# ACS_PCB.net
KiCad netlist of a schematic drawn in EAGLE
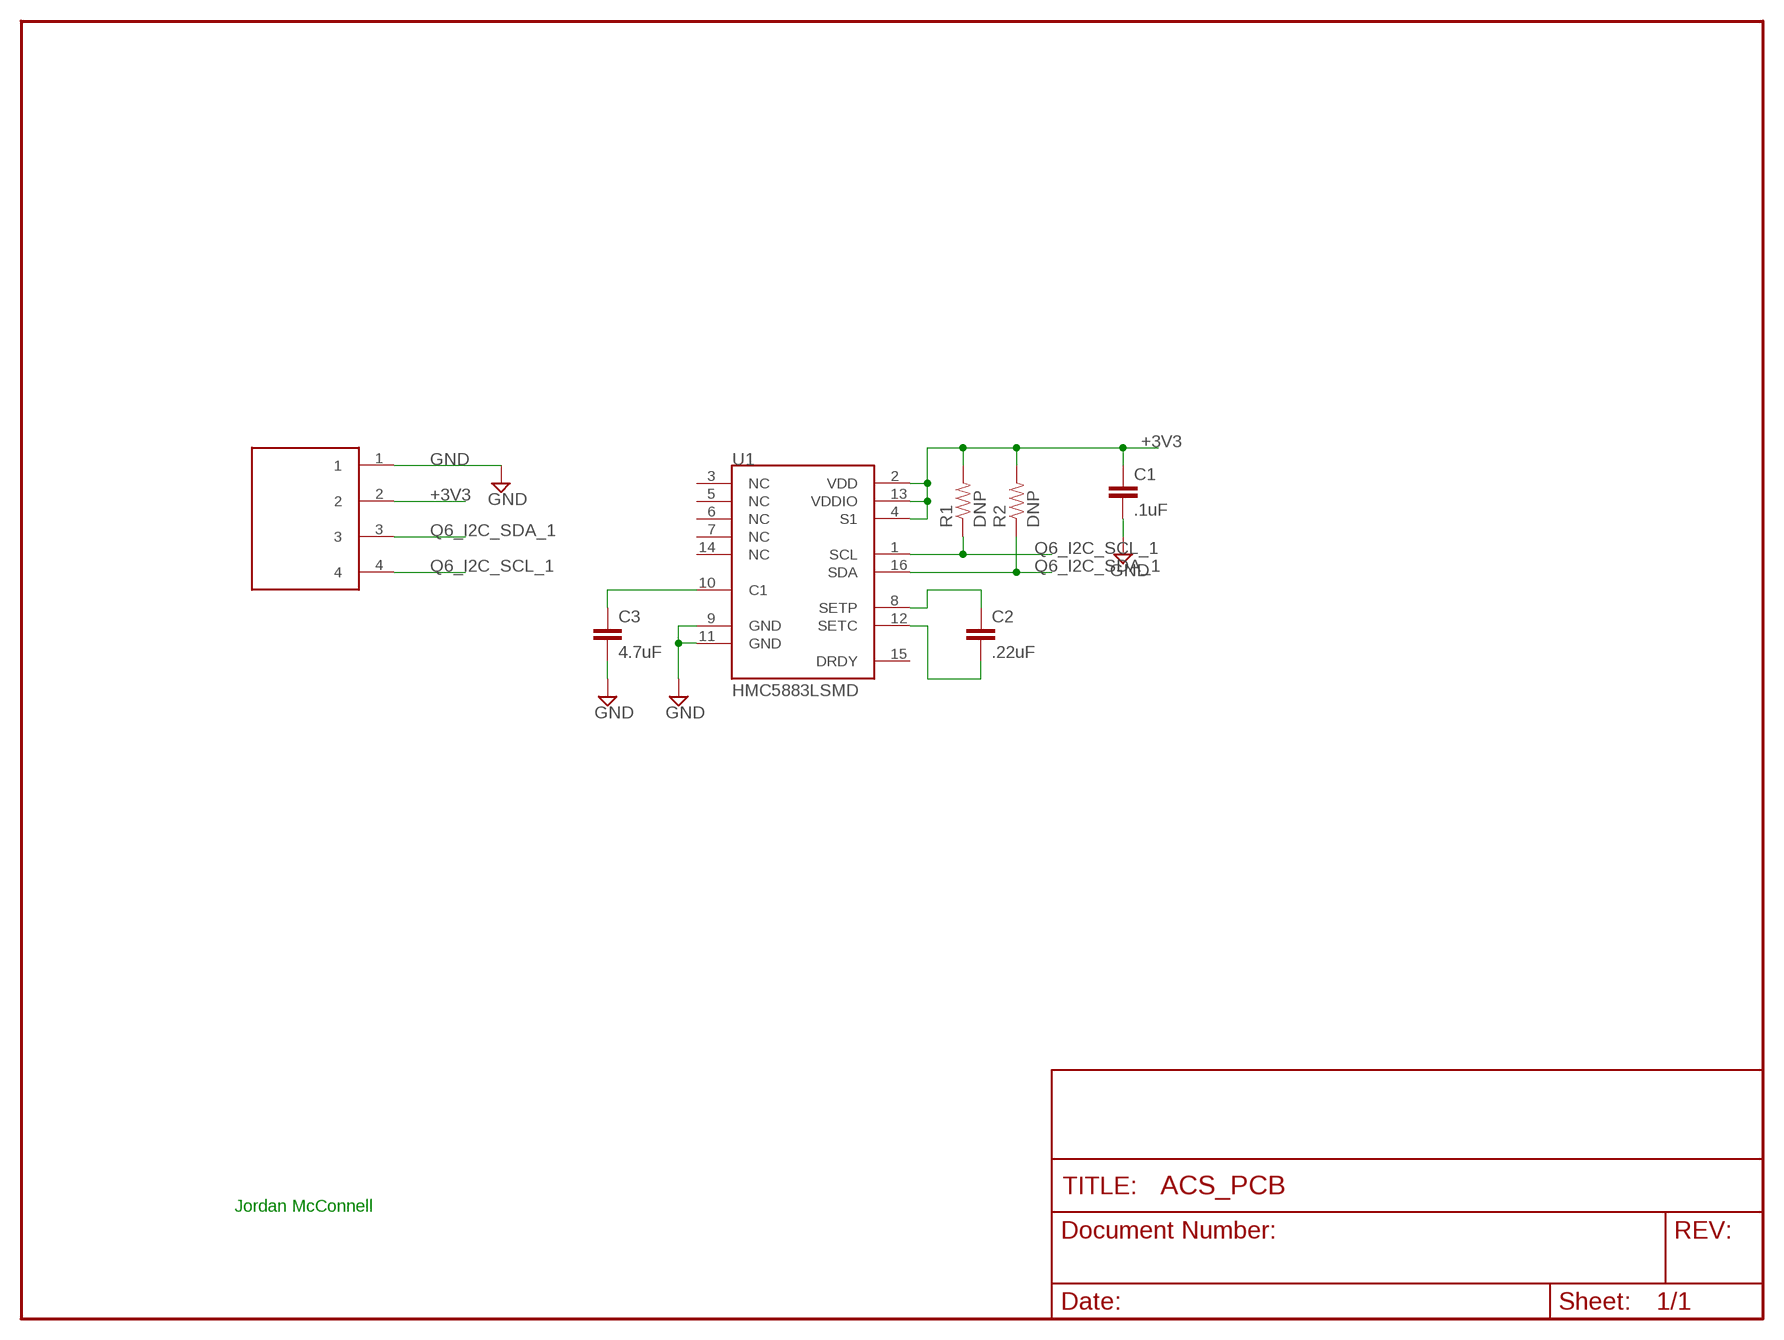
[diagram p0: schematic, sheet 1]

(export (version "E")
  (design (tool "Eeschema 10.0.6"))
  (components
    (comp (ref "C1")
      (value ".1uF")
      (footprint "eagle-import:0402-CAP")
      (libsource (lib "eagle-import") (part "CAP0402-CAP"))
    )
    (comp (ref "C2")
      (value ".22uF")
      (footprint "eagle-import:0402-CAP")
      (libsource (lib "eagle-import") (part "CAP0402-CAP"))
    )
    (comp (ref "C3")
      (value "4.7uF")
      (footprint "eagle-import:0402-CAP")
      (libsource (lib "eagle-import") (part "CAP0402-CAP"))
    )
    (comp (ref "J1")
      (value "M80-879")
      (footprint "eagle-import:M80-879")
      (libsource (lib "eagle-import") (part "M80-879"))
    )
    (comp (ref "R1")
      (value "DNP")
      (footprint "eagle-import:0402-RES")
      (libsource (lib "eagle-import") (part "RESISTOR0402-RES"))
    )
    (comp (ref "R2")
      (value "DNP")
      (footprint "eagle-import:0402-RES")
      (libsource (lib "eagle-import") (part "RESISTOR0402-RES"))
    )
    (comp (ref "U1")
      (value "HMC5883LSMD")
      (footprint "eagle-import:16LPCC")
      (libsource (lib "eagle-import") (part "HMC5883LSMD"))
    )
  )
  (nets
    (net (code "1") (name "/+3V3") (class "Default")
      (node (ref "C1") (pin "1") (pinfunction "1_1") (pintype "passive"))
      (node (ref "J1") (pin "2") (pinfunction "2_2") (pintype "bidirectional"))
      (node (ref "R1") (pin "2") (pinfunction "2_2") (pintype "passive"))
      (node (ref "R2") (pin "2") (pinfunction "2_2") (pintype "passive"))
      (node (ref "U1") (pin "13") (pinfunction "VDDIO_13") (pintype "bidirectional"))
      (node (ref "U1") (pin "2") (pinfunction "VDD_2") (pintype "bidirectional"))
      (node (ref "U1") (pin "4") (pinfunction "S1_4") (pintype "bidirectional"))
    )
    (net (code "2") (name "/Q6_I2C_SCL_1") (class "Default")
      (node (ref "J1") (pin "4") (pinfunction "4_4") (pintype "bidirectional"))
      (node (ref "R1") (pin "1") (pinfunction "1_1") (pintype "passive"))
      (node (ref "U1") (pin "1") (pinfunction "SCL_1") (pintype "bidirectional"))
    )
    (net (code "3") (name "/Q6_I2C_SDA_1") (class "Default")
      (node (ref "J1") (pin "3") (pinfunction "3_3") (pintype "bidirectional"))
      (node (ref "R2") (pin "1") (pinfunction "1_1") (pintype "passive"))
      (node (ref "U1") (pin "16") (pinfunction "SDA_16") (pintype "bidirectional"))
    )
    (net (code "4") (name "GND") (class "Default")
      (node (ref "C1") (pin "2") (pinfunction "2_2") (pintype "passive"))
      (node (ref "C3") (pin "2") (pinfunction "2_2") (pintype "passive"))
      (node (ref "J1") (pin "1") (pinfunction "1_1") (pintype "bidirectional"))
      (node (ref "U1") (pin "11") (pinfunction "GND_11") (pintype "bidirectional"))
      (node (ref "U1") (pin "9") (pinfunction "GND_9") (pintype "bidirectional"))
    )
    (net (code "5") (name "Net-(U1-C1)") (class "Default")
      (node (ref "C3") (pin "1") (pinfunction "1_1") (pintype "passive"))
      (node (ref "U1") (pin "10") (pinfunction "C1_10") (pintype "bidirectional"))
    )
    (net (code "6") (name "Net-(U1-SETC)") (class "Default")
      (node (ref "C2") (pin "2") (pinfunction "2_2") (pintype "passive"))
      (node (ref "U1") (pin "12") (pinfunction "SETC_12") (pintype "bidirectional"))
    )
    (net (code "7") (name "Net-(U1-SETP)") (class "Default")
      (node (ref "C2") (pin "1") (pinfunction "1_1") (pintype "passive"))
      (node (ref "U1") (pin "8") (pinfunction "SETP_8") (pintype "bidirectional"))
    )
    (net (code "8") (name "unconnected-(U1-DRDY-Pad15)") (class "Default")
      (node (ref "U1") (pin "15") (pinfunction "DRDY_15") (pintype "bidirectional"))
    )
    (net (code "9") (name "unconnected-(U1-NC-Pad3)") (class "Default")
      (node (ref "U1") (pin "3") (pinfunction "NC_3") (pintype "bidirectional"))
    )
    (net (code "10") (name "unconnected-(U1-NC-Pad5)") (class "Default")
      (node (ref "U1") (pin "5") (pinfunction "NC_5") (pintype "bidirectional"))
    )
    (net (code "11") (name "unconnected-(U1-NC-Pad6)") (class "Default")
      (node (ref "U1") (pin "6") (pinfunction "NC_6") (pintype "bidirectional"))
    )
    (net (code "12") (name "unconnected-(U1-NC-Pad7)") (class "Default")
      (node (ref "U1") (pin "7") (pinfunction "NC_7") (pintype "bidirectional"))
    )
    (net (code "13") (name "unconnected-(U1-NC-Pad14)") (class "Default")
      (node (ref "U1") (pin "14") (pinfunction "NC_14") (pintype "bidirectional"))
    )
  )
)
